# ir-sensor-breakout-mk-2_3-smd.net
KiCad netlist of a schematic drawn in EAGLE
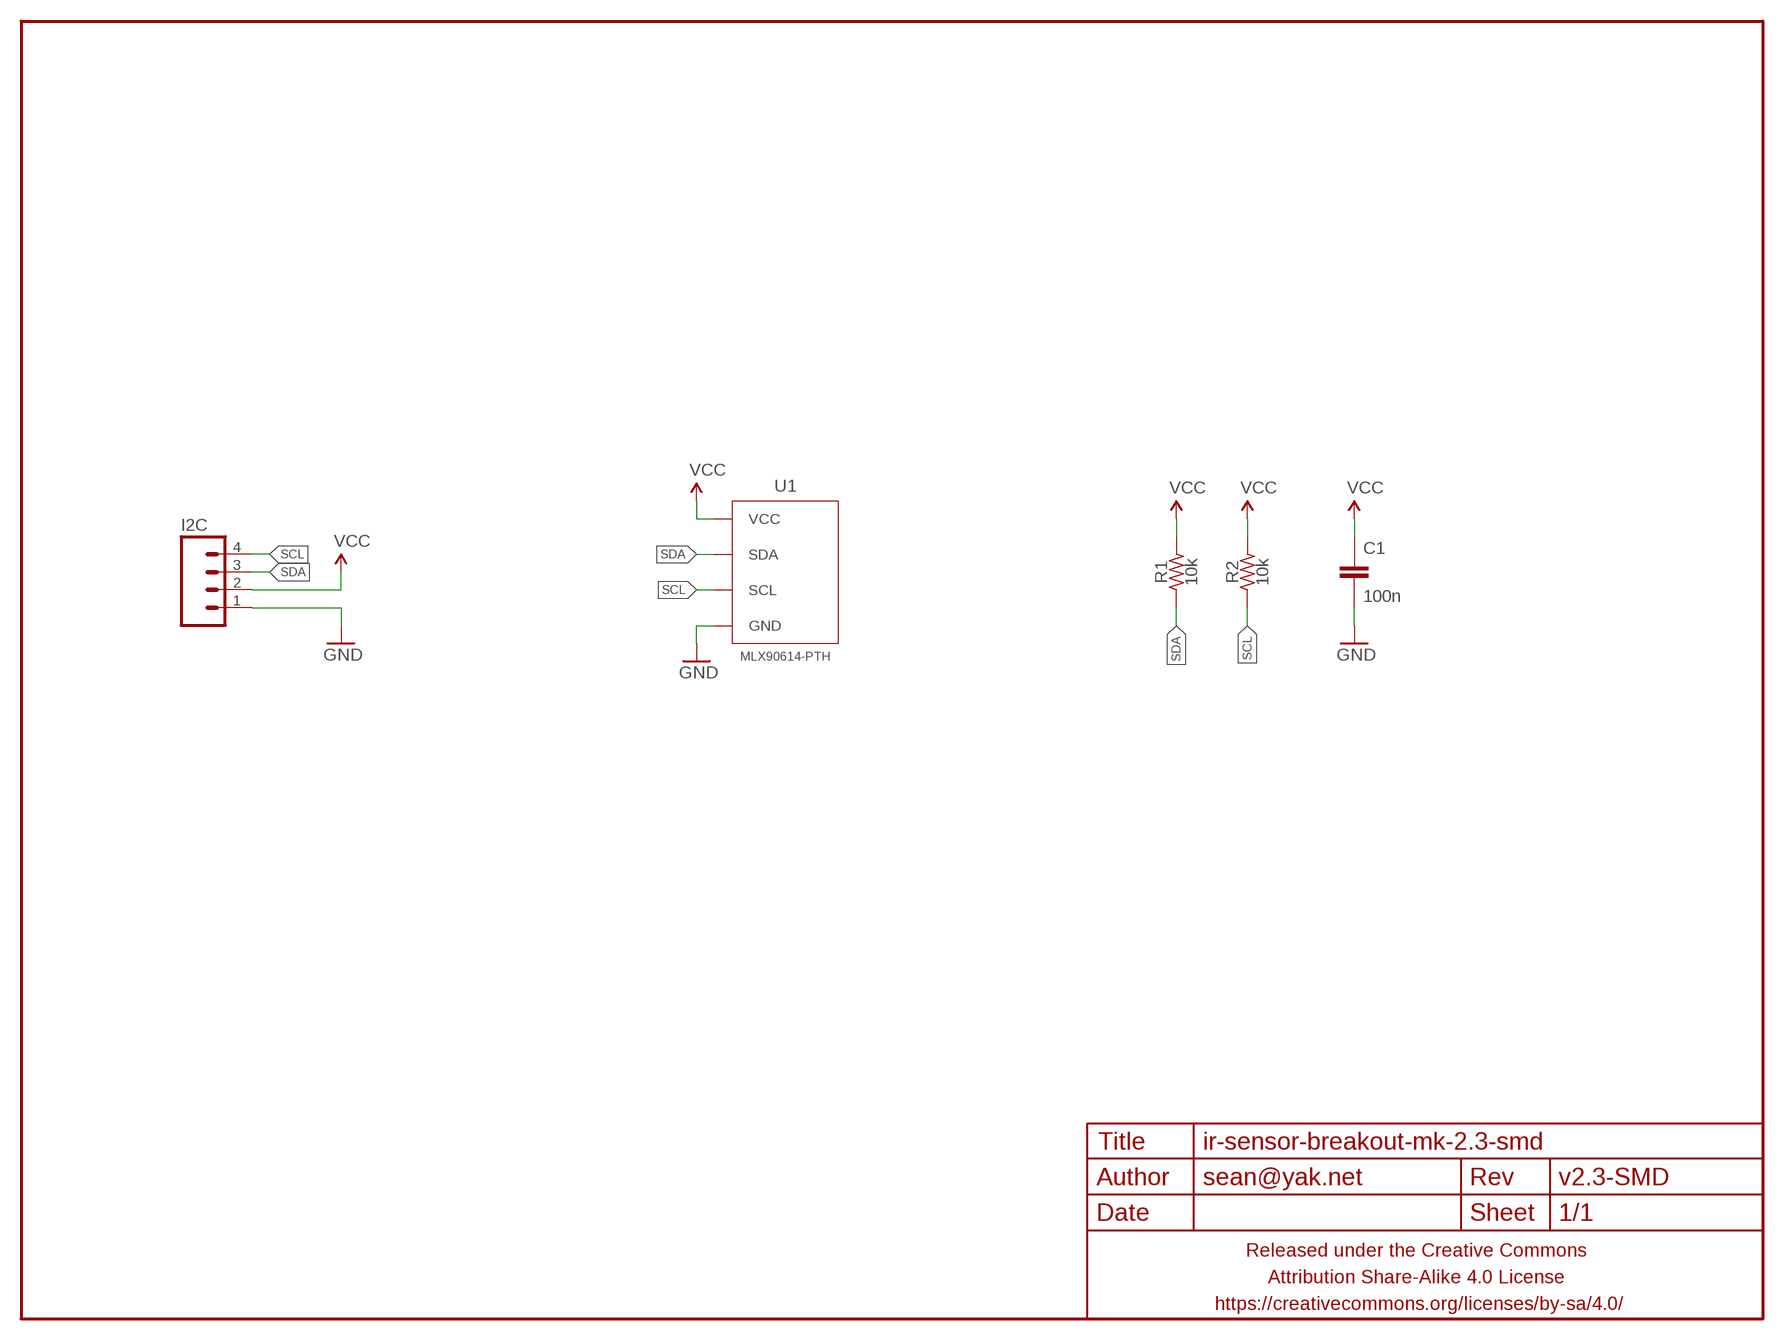
[diagram p0: schematic, sheet 1]

(export (version "E")
  (design (tool "Eeschema 10.0.6"))
  (components
    (comp (ref "C1")
      (value "100n")
      (footprint "eagle-import:C0805")
      (libsource (lib "eagle-import") (part "CAPACITOR-CERAMICC0805"))
    )
    (comp (ref "FRAME1")
      (value "FRAME-LETTERNO_PACKAGE")
      (footprint "eagle-import:DUMMY")
      (fields (field (name "DESIGNER") "sean@yak.net") (field (name "VERSION") "v2.3-SMD"))
      (libsource (lib "eagle-import") (part "FRAME-LETTERNO_PACKAGE"))
    )
    (comp (ref "I2C")
      (value "M04JST-PTH-VERT")
      (footprint "eagle-import:JST-4-PH-VERT-PTH")
      (libsource (lib "eagle-import") (part "M04JST-PTH-VERT"))
    )
    (comp (ref "R1")
      (value "10k")
      (footprint "eagle-import:R0805")
      (libsource (lib "eagle-import") (part "RESISTORR0805"))
    )
    (comp (ref "R2")
      (value "10k")
      (footprint "eagle-import:R0805")
      (libsource (lib "eagle-import") (part "RESISTORR0805"))
    )
    (comp (ref "U1")
      (value "MLX90614-PTH")
      (footprint "eagle-import:TO-39-4")
      (libsource (lib "eagle-import") (part "MLX906145V-PTH"))
    )
  )
  (nets
    (net (code "1") (name "GND") (class "Default")
      (node (ref "C1") (pin "2") (pinfunction "2_2") (pintype "passive"))
      (node (ref "I2C") (pin "1") (pinfunction "1_1") (pintype "passive"))
      (node (ref "U1") (pin "4") (pinfunction "GND_4") (pintype "bidirectional"))
    )
    (net (code "2") (name "SCL") (class "Default")
      (node (ref "I2C") (pin "4") (pinfunction "4_4") (pintype "passive"))
      (node (ref "R2") (pin "1") (pinfunction "1_1") (pintype "passive"))
      (node (ref "U1") (pin "1") (pinfunction "SCL_1") (pintype "bidirectional"))
    )
    (net (code "3") (name "SDA") (class "Default")
      (node (ref "I2C") (pin "3") (pinfunction "3_3") (pintype "passive"))
      (node (ref "R1") (pin "1") (pinfunction "1_1") (pintype "passive"))
      (node (ref "U1") (pin "2") (pinfunction "SDA_2") (pintype "bidirectional"))
    )
    (net (code "4") (name "VCC") (class "Default")
      (node (ref "C1") (pin "1") (pinfunction "1_1") (pintype "passive"))
      (node (ref "I2C") (pin "2") (pinfunction "2_2") (pintype "passive"))
      (node (ref "R1") (pin "2") (pinfunction "2_2") (pintype "passive"))
      (node (ref "R2") (pin "2") (pinfunction "2_2") (pintype "passive"))
      (node (ref "U1") (pin "3") (pinfunction "VCC_3") (pintype "bidirectional"))
    )
  )
)
